# M26_M_V1_0.net
KiCad netlist of a schematic drawn in Altium Designer
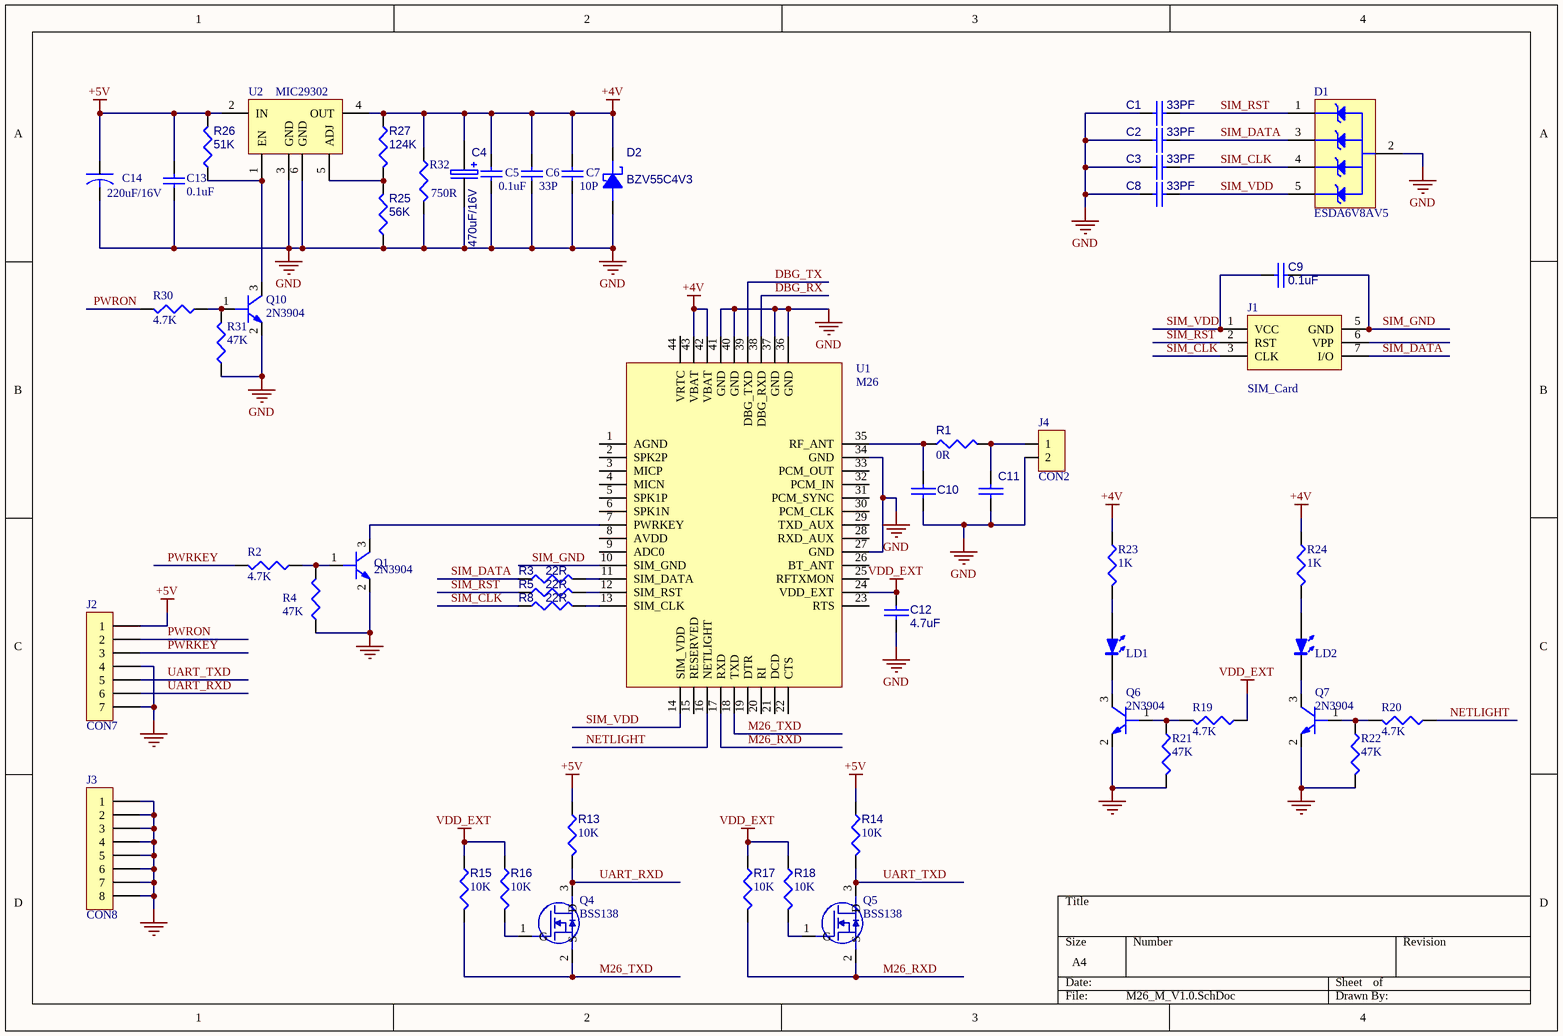
[diagram p0: M26_M_V1.0.SchDoc]

(export (version "E")
  (design (tool "Eeschema 10.0.6"))
  (components
    (comp (ref "C1")
      (value "33PF")
      (footprint "0603_C")
      (description "CAP")
      (libsource (lib "*") (part "CAP"))
    )
    (comp (ref "C2")
      (value "33PF")
      (footprint "0603_C")
      (description "CAP")
      (libsource (lib "*") (part "CAP"))
    )
    (comp (ref "C3")
      (value "33PF")
      (footprint "0603_C")
      (description "CAP")
      (libsource (lib "*") (part "CAP"))
    )
    (comp (ref "C4")
      (value "470uF/16V")
      (footprint "C_TAN_D")
      (description "E-CAP")
      (libsource (lib "*") (part "ECAP"))
    )
    (comp (ref "C5")
      (value "0.1uF")
      (footprint "0603_C")
      (description "Capacitor")
      (fields (field (name "PUBLISHER") "Altium Limited"))
      (libsource (lib "EP_MCB_V3.00") (part "Cap Semi"))
    )
    (comp (ref "C6")
      (value "33P")
      (footprint "0603_C")
      (description "Capacitor")
      (fields (field (name "PUBLISHER") "Altium Limited"))
      (libsource (lib "EP_MCB_V3.00") (part "Cap Semi"))
    )
    (comp (ref "C7")
      (value "10P")
      (footprint "0603_C")
      (description "Capacitor")
      (fields (field (name "PUBLISHER") "Altium Limited"))
      (libsource (lib "EP_MCB_V3.00") (part "Cap Semi"))
    )
    (comp (ref "C8")
      (value "33PF")
      (footprint "0603_C")
      (description "CAP")
      (libsource (lib "*") (part "CAP"))
    )
    (comp (ref "C9")
      (value "0.1uF")
      (footprint "0603_C")
      (description "CAP")
      (libsource (lib "*") (part "CAP"))
    )
    (comp (ref "C10")
      (value "NC")
      (footprint "0603_C")
      (description "CAP")
      (libsource (lib "") (part "CAP_1"))
    )
    (comp (ref "C11")
      (value "NC")
      (footprint "0603_C")
      (description "CAP")
      (libsource (lib "") (part "CAP_1"))
    )
    (comp (ref "C12")
      (value "4.7uF")
      (footprint "0603_C")
      (description "CAP")
      (libsource (lib "") (part "CAP_1"))
    )
    (comp (ref "C13")
      (value "0.1uF")
      (footprint "0603_C")
      (description "Capacitor")
      (fields (field (name "PUBLISHER") "Altium Limited"))
      (libsource (lib "EP_MCB_V3.00") (part "Cap Semi"))
    )
    (comp (ref "C14")
      (value "220uF/16V")
      (footprint "C_TAN_D")
      (libsource (lib "EM_SENSOR_V3.01") (part "C"))
    )
    (comp (ref "D1")
      (value "ESDA6V8AV5")
      (footprint "SOT-553")
      (libsource (lib "MySchlib") (part "ESDA6V8AV5"))
    )
    (comp (ref "D2")
      (value "BZV55C4V3")
      (footprint "SOD-80")
      (libsource (lib "EP_MCB_V4.1") (part "DIODE SCHOTTKY"))
    )
    (comp (ref "J1")
      (value "SIM_Card")
      (footprint "MicroSIM-6")
      (libsource (lib "MySchlib") (part "SIM_Card"))
    )
    (comp (ref "J2") (value "CON7") (footprint "SIP7") (libsource (lib "MySchlib") (part "CON7")))
    (comp (ref "J3") (value "CON8") (footprint "SIP-8") (libsource (lib "MySchlib") (part "CON8")))
    (comp (ref "J4") (value "CON2") (footprint "RF-Z") (libsource (lib "MySchlib") (part "CON2")))
    (comp (ref "LD1")
      (value "WHITE")
      (footprint "LED_0603")
      (description "LED")
      (libsource (lib "*") (part "LED"))
    )
    (comp (ref "LD2")
      (value "WHITE")
      (footprint "LED_0603")
      (description "LED")
      (libsource (lib "*") (part "LED"))
    )
    (comp (ref "Q1") (value "2N3904") (footprint "SOT23") (libsource (lib "MySchlib") (part "NPN")))
    (comp (ref "Q4")
      (value "BSS138")
      (footprint "SOT23")
      (description "N-Channel Enhancement MOSFET")
      (libsource (lib "EP_MCB_V6.0") (part "N-Channel Enhancement MOSFET"))
    )
    (comp (ref "Q5")
      (value "BSS138")
      (footprint "SOT23")
      (description "N-Channel Enhancement MOSFET")
      (libsource (lib "EP_MCB_V6.0") (part "N-Channel Enhancement MOSFET"))
    )
    (comp (ref "Q6") (value "2N3904") (footprint "SOT23") (libsource (lib "MySchlib") (part "NPN")))
    (comp (ref "Q7") (value "2N3904") (footprint "SOT23") (libsource (lib "MySchlib") (part "NPN")))
    (comp (ref "Q10") (value "2N3904") (footprint "SOT23") (libsource (lib "MySchlib") (part "NPN")))
    (comp (ref "R1")
      (value "0R")
      (footprint "0603_R")
      (description "Resistor")
      (fields (field (name "PUBLISHER") "Altium Limited"))
      (libsource (lib "EP_MCB_V6.0") (part "Res3_3"))
    )
    (comp (ref "R2") (value "4.7K") (footprint "0603_R") (libsource (lib "") (part "RES1_1")))
    (comp (ref "R3")
      (value "22R")
      (footprint "0603_R")
      (description "RESISTOR")
      (libsource (lib "*") (part "R0.25W"))
    )
    (comp (ref "R4") (value "47K") (footprint "0603_R") (libsource (lib "") (part "RES1_1")))
    (comp (ref "R5")
      (value "22R")
      (footprint "0603_R")
      (description "RESISTOR")
      (libsource (lib "*") (part "R0.25W"))
    )
    (comp (ref "R8")
      (value "22R")
      (footprint "0603_R")
      (description "RESISTOR")
      (libsource (lib "*") (part "R0.25W"))
    )
    (comp (ref "R13")
      (value "10K")
      (footprint "0603_R")
      (description "Resistor")
      (fields (field (name "PUBLISHER") "Altium Limited"))
      (libsource (lib "EP_MCB_V6.0") (part "Res3_3"))
    )
    (comp (ref "R14")
      (value "10K")
      (footprint "0603_R")
      (description "Resistor")
      (fields (field (name "PUBLISHER") "Altium Limited"))
      (libsource (lib "EP_MCB_V6.0") (part "Res3_3"))
    )
    (comp (ref "R15")
      (value "10K")
      (footprint "0603_R")
      (description "Resistor")
      (fields (field (name "PUBLISHER") "Altium Limited"))
      (libsource (lib "EP_MCB_V6.0") (part "Res3_3"))
    )
    (comp (ref "R16")
      (value "10K")
      (footprint "0603_R")
      (description "Resistor")
      (fields (field (name "PUBLISHER") "Altium Limited"))
      (libsource (lib "EP_MCB_V6.0") (part "Res3_3"))
    )
    (comp (ref "R17")
      (value "10K")
      (footprint "0603_R")
      (description "Resistor")
      (fields (field (name "PUBLISHER") "Altium Limited"))
      (libsource (lib "EP_MCB_V6.0") (part "Res3_3"))
    )
    (comp (ref "R18")
      (value "10K")
      (footprint "0603_R")
      (description "Resistor")
      (fields (field (name "PUBLISHER") "Altium Limited"))
      (libsource (lib "EP_MCB_V6.0") (part "Res3_3"))
    )
    (comp (ref "R19") (value "4.7K") (footprint "0603_R") (libsource (lib "") (part "RES1_1")))
    (comp (ref "R20") (value "4.7K") (footprint "0603_R") (libsource (lib "") (part "RES1_1")))
    (comp (ref "R21") (value "47K") (footprint "0603_R") (libsource (lib "") (part "RES1_1")))
    (comp (ref "R22") (value "47K") (footprint "0603_R") (libsource (lib "") (part "RES1_1")))
    (comp (ref "R23") (value "1K") (footprint "0603_R") (libsource (lib "") (part "RES1_1")))
    (comp (ref "R24") (value "1K") (footprint "0603_R") (libsource (lib "") (part "RES1_1")))
    (comp (ref "R25")
      (value "56K")
      (footprint "0603_R")
      (description "RESISTOR")
      (libsource (lib "*") (part "R0.25W"))
    )
    (comp (ref "R26")
      (value "51K")
      (footprint "0603_R")
      (description "RESISTOR")
      (libsource (lib "*") (part "R0.25W"))
    )
    (comp (ref "R27")
      (value "124K")
      (footprint "0603_R")
      (description "RESISTOR")
      (libsource (lib "*") (part "R0.25W"))
    )
    (comp (ref "R30") (value "4.7K") (footprint "0603_R") (libsource (lib "") (part "RES1_1")))
    (comp (ref "R31") (value "47K") (footprint "0603_R") (libsource (lib "") (part "RES1_1")))
    (comp (ref "R32") (value "750R") (footprint "0603_R") (libsource (lib "MySchlib") (part "RES1")))
    (comp (ref "U1") (value "M26") (footprint "M26") (libsource (lib "MySchlib") (part "M26")))
    (comp (ref "U2") (value "MIC29302") (footprint "TO-263-5") (libsource (lib "MySchlib") (part "MIC29302")))
  )
  (nets
    (net (code "1") (name "+4V") (class "Default")
      (node (ref "C4") (pin "1") (pinfunction "+_1") (pintype "passive"))
      (node (ref "C5") (pin "2") (pinfunction "2_2") (pintype "passive"))
      (node (ref "C6") (pin "2") (pinfunction "2_2") (pintype "passive"))
      (node (ref "C7") (pin "2") (pinfunction "2_2") (pintype "passive"))
      (node (ref "D2") (pin "2") (pinfunction "CATHODE_2") (pintype "passive"))
      (node (ref "R23") (pin "1") (pinfunction "1_1") (pintype "passive"))
      (node (ref "R24") (pin "1") (pinfunction "1_1") (pintype "passive"))
      (node (ref "R27") (pin "2") (pinfunction "2_2") (pintype "passive"))
      (node (ref "R32") (pin "2") (pinfunction "2_2") (pintype "passive"))
      (node (ref "U1") (pin "42") (pinfunction "VBAT_42") (pintype "passive"))
      (node (ref "U1") (pin "43") (pinfunction "VBAT_43") (pintype "passive"))
      (node (ref "U2") (pin "4") (pinfunction "OUT_4") (pintype "passive"))
    )
    (net (code "2") (name "+5V") (class "Default")
      (node (ref "C13") (pin "2") (pinfunction "2_2") (pintype "passive"))
      (node (ref "C14") (pin "1") (pinfunction "1_1") (pintype "passive"))
      (node (ref "J2") (pin "1") (pinfunction "1_1") (pintype "passive"))
      (node (ref "R13") (pin "1") (pinfunction "1_1") (pintype "passive"))
      (node (ref "R14") (pin "1") (pinfunction "1_1") (pintype "passive"))
      (node (ref "R26") (pin "1") (pinfunction "1_1") (pintype "passive"))
      (node (ref "U2") (pin "2") (pinfunction "IN_2") (pintype "passive"))
    )
    (net (code "3") (name "/DBG_RX") (class "Default")
      (node (ref "U1") (pin "38") (pinfunction "DBG_RXD_38") (pintype "passive"))
    )
    (net (code "4") (name "/DBG_TX") (class "Default")
      (node (ref "U1") (pin "39") (pinfunction "DBG_TXD_39") (pintype "passive"))
    )
    (net (code "5") (name "/M26_RXD") (class "Default")
      (node (ref "Q5") (pin "2") (pinfunction "S_2") (pintype "passive"))
      (node (ref "R17") (pin "2") (pinfunction "2_2") (pintype "passive"))
      (node (ref "U1") (pin "17") (pinfunction "RXD_17") (pintype "passive"))
    )
    (net (code "6") (name "/M26_TXD") (class "Default")
      (node (ref "Q4") (pin "2") (pinfunction "S_2") (pintype "passive"))
      (node (ref "R15") (pin "2") (pinfunction "2_2") (pintype "passive"))
      (node (ref "U1") (pin "18") (pinfunction "TXD_18") (pintype "passive"))
    )
    (net (code "7") (name "/NETLIGHT") (class "Default")
      (node (ref "R20") (pin "1") (pinfunction "1_1") (pintype "passive"))
      (node (ref "U1") (pin "16") (pinfunction "NETLIGHT_16") (pintype "passive"))
    )
    (net (code "8") (name "/PWRKEY") (class "Default")
      (node (ref "J2") (pin "3") (pinfunction "3_3") (pintype "passive"))
      (node (ref "R2") (pin "1") (pinfunction "1_1") (pintype "passive"))
    )
    (net (code "9") (name "/PWRON") (class "Default")
      (node (ref "J2") (pin "2") (pinfunction "2_2") (pintype "passive"))
      (node (ref "R30") (pin "1") (pinfunction "1_1") (pintype "passive"))
    )
    (net (code "10") (name "/SIM_CLK") (class "Default")
      (node (ref "C3") (pin "2") (pinfunction "2_2") (pintype "passive"))
      (node (ref "D1") (pin "4") (pinfunction "4_4") (pintype "passive"))
      (node (ref "J1") (pin "3") (pinfunction "CLK_3") (pintype "passive"))
      (node (ref "R8") (pin "1") (pinfunction "1_1") (pintype "passive"))
    )
    (net (code "11") (name "/SIM_DATA") (class "Default")
      (node (ref "C2") (pin "2") (pinfunction "2_2") (pintype "passive"))
      (node (ref "D1") (pin "3") (pinfunction "3_3") (pintype "passive"))
      (node (ref "J1") (pin "7") (pinfunction "I/O_7") (pintype "passive"))
      (node (ref "R3") (pin "1") (pinfunction "1_1") (pintype "passive"))
    )
    (net (code "12") (name "/SIM_GND") (class "Default")
      (node (ref "C9") (pin "2") (pinfunction "2_2") (pintype "passive"))
      (node (ref "J1") (pin "5") (pinfunction "GND_5") (pintype "passive"))
      (node (ref "U1") (pin "10") (pinfunction "SIM_GND_10") (pintype "passive"))
    )
    (net (code "13") (name "/SIM_RST") (class "Default")
      (node (ref "C1") (pin "2") (pinfunction "2_2") (pintype "passive"))
      (node (ref "D1") (pin "1") (pinfunction "1_1") (pintype "passive"))
      (node (ref "J1") (pin "2") (pinfunction "RST_2") (pintype "passive"))
      (node (ref "R5") (pin "1") (pinfunction "1_1") (pintype "passive"))
    )
    (net (code "14") (name "/SIM_VDD") (class "Default")
      (node (ref "C8") (pin "2") (pinfunction "2_2") (pintype "passive"))
      (node (ref "C9") (pin "1") (pinfunction "1_1") (pintype "passive"))
      (node (ref "D1") (pin "5") (pinfunction "5_5") (pintype "passive"))
      (node (ref "J1") (pin "1") (pinfunction "VCC_1") (pintype "passive"))
      (node (ref "U1") (pin "14") (pinfunction "SIM_VDD_14") (pintype "passive"))
    )
    (net (code "15") (name "/UART_RXD") (class "Default")
      (node (ref "J2") (pin "6") (pinfunction "6_6") (pintype "passive"))
      (node (ref "Q4") (pin "3") (pinfunction "D_3") (pintype "passive"))
      (node (ref "R13") (pin "2") (pinfunction "2_2") (pintype "passive"))
    )
    (net (code "16") (name "/UART_TXD") (class "Default")
      (node (ref "J2") (pin "5") (pinfunction "5_5") (pintype "passive"))
      (node (ref "Q5") (pin "3") (pinfunction "D_3") (pintype "passive"))
      (node (ref "R14") (pin "2") (pinfunction "2_2") (pintype "passive"))
    )
    (net (code "17") (name "GND") (class "Default")
      (node (ref "C1") (pin "1") (pinfunction "1_1") (pintype "passive"))
      (node (ref "C10") (pin "2") (pinfunction "2_2") (pintype "passive"))
      (node (ref "C11") (pin "2") (pinfunction "2_2") (pintype "passive"))
      (node (ref "C12") (pin "2") (pinfunction "2_2") (pintype "passive"))
      (node (ref "C13") (pin "1") (pinfunction "1_1") (pintype "passive"))
      (node (ref "C14") (pin "2") (pinfunction "2_2") (pintype "passive"))
      (node (ref "C2") (pin "1") (pinfunction "1_1") (pintype "passive"))
      (node (ref "C3") (pin "1") (pinfunction "1_1") (pintype "passive"))
      (node (ref "C4") (pin "2") (pinfunction "-_2") (pintype "passive"))
      (node (ref "C5") (pin "1") (pinfunction "1_1") (pintype "passive"))
      (node (ref "C6") (pin "1") (pinfunction "1_1") (pintype "passive"))
      (node (ref "C7") (pin "1") (pinfunction "1_1") (pintype "passive"))
      (node (ref "C8") (pin "1") (pinfunction "1_1") (pintype "passive"))
      (node (ref "D1") (pin "2") (pinfunction "2_2") (pintype "passive"))
      (node (ref "D2") (pin "1") (pinfunction "ANODE_1") (pintype "passive"))
      (node (ref "J2") (pin "4") (pinfunction "4_4") (pintype "passive"))
      (node (ref "J2") (pin "7") (pinfunction "7_7") (pintype "passive"))
      (node (ref "J3") (pin "1") (pinfunction "1_1") (pintype "passive"))
      (node (ref "J3") (pin "2") (pinfunction "2_2") (pintype "passive"))
      (node (ref "J3") (pin "3") (pinfunction "3_3") (pintype "passive"))
      (node (ref "J3") (pin "4") (pinfunction "4_4") (pintype "passive"))
      (node (ref "J3") (pin "5") (pinfunction "5_5") (pintype "passive"))
      (node (ref "J3") (pin "6") (pinfunction "6_6") (pintype "passive"))
      (node (ref "J3") (pin "7") (pinfunction "7_7") (pintype "passive"))
      (node (ref "J3") (pin "8") (pinfunction "8_8") (pintype "passive"))
      (node (ref "J4") (pin "2") (pinfunction "2_2") (pintype "passive"))
      (node (ref "Q1") (pin "2") (pinfunction "EMITTER_2") (pintype "passive"))
      (node (ref "Q10") (pin "2") (pinfunction "EMITTER_2") (pintype "passive"))
      (node (ref "Q6") (pin "2") (pinfunction "EMITTER_2") (pintype "passive"))
      (node (ref "Q7") (pin "2") (pinfunction "EMITTER_2") (pintype "passive"))
      (node (ref "R21") (pin "2") (pinfunction "2_2") (pintype "passive"))
      (node (ref "R22") (pin "2") (pinfunction "2_2") (pintype "passive"))
      (node (ref "R25") (pin "2") (pinfunction "2_2") (pintype "passive"))
      (node (ref "R31") (pin "2") (pinfunction "2_2") (pintype "passive"))
      (node (ref "R32") (pin "1") (pinfunction "1_1") (pintype "passive"))
      (node (ref "R4") (pin "2") (pinfunction "2_2") (pintype "passive"))
      (node (ref "U1") (pin "27") (pinfunction "GND_27") (pintype "passive"))
      (node (ref "U1") (pin "34") (pinfunction "GND_34") (pintype "passive"))
      (node (ref "U1") (pin "36") (pinfunction "GND_36") (pintype "passive"))
      (node (ref "U1") (pin "37") (pinfunction "GND_37") (pintype "passive"))
      (node (ref "U1") (pin "40") (pinfunction "GND_40") (pintype "passive"))
      (node (ref "U1") (pin "41") (pinfunction "GND_41") (pintype "passive"))
      (node (ref "U2") (pin "3") (pinfunction "GND_3") (pintype "passive"))
      (node (ref "U2") (pin "6") (pinfunction "GND_6") (pintype "passive"))
    )
    (net (code "18") (name "Net-(C11-Pad1)") (class "Default")
      (node (ref "C11") (pin "1") (pinfunction "1_1") (pintype "passive"))
      (node (ref "J4") (pin "1") (pinfunction "1_1") (pintype "passive"))
      (node (ref "R1") (pin "2") (pinfunction "2_2") (pintype "passive"))
    )
    (net (code "19") (name "Net-(LD1-PadA)") (class "Default")
      (node (ref "LD1") (pin "A") (pinfunction "A_A") (pintype "passive"))
      (node (ref "R23") (pin "2") (pinfunction "2_2") (pintype "passive"))
    )
    (net (code "20") (name "Net-(LD2-PadA)") (class "Default")
      (node (ref "LD2") (pin "A") (pinfunction "A_A") (pintype "passive"))
      (node (ref "R24") (pin "2") (pinfunction "2_2") (pintype "passive"))
    )
    (net (code "21") (name "Net-(Q1-BASE)") (class "Default")
      (node (ref "Q1") (pin "1") (pinfunction "BASE_1") (pintype "passive"))
      (node (ref "R2") (pin "2") (pinfunction "2_2") (pintype "passive"))
      (node (ref "R4") (pin "1") (pinfunction "1_1") (pintype "passive"))
    )
    (net (code "22") (name "Net-(Q1-COLLECTOR)") (class "Default")
      (node (ref "Q1") (pin "3") (pinfunction "COLLECTOR_3") (pintype "passive"))
      (node (ref "U1") (pin "7") (pinfunction "PWRKEY_7") (pintype "passive"))
    )
    (net (code "23") (name "Net-(Q4-G)") (class "Default")
      (node (ref "Q4") (pin "1") (pinfunction "G_1") (pintype "passive"))
      (node (ref "R16") (pin "2") (pinfunction "2_2") (pintype "passive"))
    )
    (net (code "24") (name "Net-(Q5-G)") (class "Default")
      (node (ref "Q5") (pin "1") (pinfunction "G_1") (pintype "passive"))
      (node (ref "R18") (pin "2") (pinfunction "2_2") (pintype "passive"))
    )
    (net (code "25") (name "Net-(Q6-BASE)") (class "Default")
      (node (ref "Q6") (pin "1") (pinfunction "BASE_1") (pintype "passive"))
      (node (ref "R19") (pin "2") (pinfunction "2_2") (pintype "passive"))
      (node (ref "R21") (pin "1") (pinfunction "1_1") (pintype "passive"))
    )
    (net (code "26") (name "Net-(Q6-COLLECTOR)") (class "Default")
      (node (ref "LD1") (pin "K") (pinfunction "K_K") (pintype "passive"))
      (node (ref "Q6") (pin "3") (pinfunction "COLLECTOR_3") (pintype "passive"))
    )
    (net (code "27") (name "Net-(Q7-BASE)") (class "Default")
      (node (ref "Q7") (pin "1") (pinfunction "BASE_1") (pintype "passive"))
      (node (ref "R20") (pin "2") (pinfunction "2_2") (pintype "passive"))
      (node (ref "R22") (pin "1") (pinfunction "1_1") (pintype "passive"))
    )
    (net (code "28") (name "Net-(Q7-COLLECTOR)") (class "Default")
      (node (ref "LD2") (pin "K") (pinfunction "K_K") (pintype "passive"))
      (node (ref "Q7") (pin "3") (pinfunction "COLLECTOR_3") (pintype "passive"))
    )
    (net (code "29") (name "Net-(Q10-BASE)") (class "Default")
      (node (ref "Q10") (pin "1") (pinfunction "BASE_1") (pintype "passive"))
      (node (ref "R30") (pin "2") (pinfunction "2_2") (pintype "passive"))
      (node (ref "R31") (pin "1") (pinfunction "1_1") (pintype "passive"))
    )
    (net (code "30") (name "Net-(Q10-COLLECTOR)") (class "Default")
      (node (ref "Q10") (pin "3") (pinfunction "COLLECTOR_3") (pintype "passive"))
      (node (ref "R26") (pin "2") (pinfunction "2_2") (pintype "passive"))
      (node (ref "U2") (pin "1") (pinfunction "EN_1") (pintype "passive"))
    )
    (net (code "31") (name "Net-(U1-RF_ANT)") (class "Default")
      (node (ref "C10") (pin "1") (pinfunction "1_1") (pintype "passive"))
      (node (ref "R1") (pin "1") (pinfunction "1_1") (pintype "passive"))
      (node (ref "U1") (pin "35") (pinfunction "RF_ANT_35") (pintype "passive"))
    )
    (net (code "32") (name "Net-(U1-SIM_CLK)") (class "Default")
      (node (ref "R8") (pin "2") (pinfunction "2_2") (pintype "passive"))
      (node (ref "U1") (pin "13") (pinfunction "SIM_CLK_13") (pintype "passive"))
    )
    (net (code "33") (name "Net-(U1-SIM_DATA)") (class "Default")
      (node (ref "R3") (pin "2") (pinfunction "2_2") (pintype "passive"))
      (node (ref "U1") (pin "11") (pinfunction "SIM_DATA_11") (pintype "passive"))
    )
    (net (code "34") (name "Net-(U1-SIM_RST)") (class "Default")
      (node (ref "R5") (pin "2") (pinfunction "2_2") (pintype "passive"))
      (node (ref "U1") (pin "12") (pinfunction "SIM_RST_12") (pintype "passive"))
    )
    (net (code "35") (name "Net-(U2-ADJ)") (class "Default")
      (node (ref "R25") (pin "1") (pinfunction "1_1") (pintype "passive"))
      (node (ref "R27") (pin "1") (pinfunction "1_1") (pintype "passive"))
      (node (ref "U2") (pin "5") (pinfunction "ADJ_5") (pintype "passive"))
    )
    (net (code "36") (name "VDD_EXT") (class "Default")
      (node (ref "C12") (pin "1") (pinfunction "1_1") (pintype "passive"))
      (node (ref "R15") (pin "1") (pinfunction "1_1") (pintype "passive"))
      (node (ref "R16") (pin "1") (pinfunction "1_1") (pintype "passive"))
      (node (ref "R17") (pin "1") (pinfunction "1_1") (pintype "passive"))
      (node (ref "R18") (pin "1") (pinfunction "1_1") (pintype "passive"))
      (node (ref "R19") (pin "1") (pinfunction "1_1") (pintype "passive"))
      (node (ref "U1") (pin "24") (pinfunction "VDD_EXT_24") (pintype "passive"))
    )
    (net (code "37") (name "unconnected-(J1-VPP-Pad6)") (class "Default")
      (node (ref "J1") (pin "6") (pinfunction "VPP_6") (pintype "passive"))
    )
    (net (code "38") (name "unconnected-(U1-ADC0-Pad9)") (class "Default")
      (node (ref "U1") (pin "9") (pinfunction "ADC0_9") (pintype "passive"))
    )
    (net (code "39") (name "unconnected-(U1-AGND-Pad1)") (class "Default")
      (node (ref "U1") (pin "1") (pinfunction "AGND_1") (pintype "passive"))
    )
    (net (code "40") (name "unconnected-(U1-AVDD-Pad8)") (class "Default")
      (node (ref "U1") (pin "8") (pinfunction "AVDD_8") (pintype "passive"))
    )
    (net (code "41") (name "unconnected-(U1-BT_ANT-Pad26)") (class "Default")
      (node (ref "U1") (pin "26") (pinfunction "BT_ANT_26") (pintype "passive"))
    )
    (net (code "42") (name "unconnected-(U1-CTS-Pad22)") (class "Default")
      (node (ref "U1") (pin "22") (pinfunction "CTS_22") (pintype "passive"))
    )
    (net (code "43") (name "unconnected-(U1-DCD-Pad21)") (class "Default")
      (node (ref "U1") (pin "21") (pinfunction "DCD_21") (pintype "passive"))
    )
    (net (code "44") (name "unconnected-(U1-DTR-Pad19)") (class "Default")
      (node (ref "U1") (pin "19") (pinfunction "DTR_19") (pintype "passive"))
    )
    (net (code "45") (name "unconnected-(U1-MICN-Pad4)") (class "Default")
      (node (ref "U1") (pin "4") (pinfunction "MICN_4") (pintype "passive"))
    )
    (net (code "46") (name "unconnected-(U1-MICP-Pad3)") (class "Default")
      (node (ref "U1") (pin "3") (pinfunction "MICP_3") (pintype "passive"))
    )
    (net (code "47") (name "unconnected-(U1-PCM_CLK-Pad30)") (class "Default")
      (node (ref "U1") (pin "30") (pinfunction "PCM_CLK_30") (pintype "passive"))
    )
    (net (code "48") (name "unconnected-(U1-PCM_IN-Pad32)") (class "Default")
      (node (ref "U1") (pin "32") (pinfunction "PCM_IN_32") (pintype "passive"))
    )
    (net (code "49") (name "unconnected-(U1-PCM_OUT-Pad33)") (class "Default")
      (node (ref "U1") (pin "33") (pinfunction "PCM_OUT_33") (pintype "passive"))
    )
    (net (code "50") (name "unconnected-(U1-PCM_SYNC-Pad31)") (class "Default")
      (node (ref "U1") (pin "31") (pinfunction "PCM_SYNC_31") (pintype "passive"))
    )
    (net (code "51") (name "unconnected-(U1-RESERVED-Pad15)") (class "Default")
      (node (ref "U1") (pin "15") (pinfunction "RESERVED_15") (pintype "passive"))
    )
    (net (code "52") (name "unconnected-(U1-RFTXMON-Pad25)") (class "Default")
      (node (ref "U1") (pin "25") (pinfunction "RFTXMON_25") (pintype "passive"))
    )
    (net (code "53") (name "unconnected-(U1-RI-Pad20)") (class "Default")
      (node (ref "U1") (pin "20") (pinfunction "RI_20") (pintype "passive"))
    )
    (net (code "54") (name "unconnected-(U1-RTS-Pad23)") (class "Default")
      (node (ref "U1") (pin "23") (pinfunction "RTS_23") (pintype "passive"))
    )
    (net (code "55") (name "unconnected-(U1-RXD_AUX-Pad28)") (class "Default")
      (node (ref "U1") (pin "28") (pinfunction "RXD_AUX_28") (pintype "passive"))
    )
    (net (code "56") (name "unconnected-(U1-SPK1N-Pad6)") (class "Default")
      (node (ref "U1") (pin "6") (pinfunction "SPK1N_6") (pintype "passive"))
    )
    (net (code "57") (name "unconnected-(U1-SPK1P-Pad5)") (class "Default")
      (node (ref "U1") (pin "5") (pinfunction "SPK1P_5") (pintype "passive"))
    )
    (net (code "58") (name "unconnected-(U1-SPK2P-Pad2)") (class "Default")
      (node (ref "U1") (pin "2") (pinfunction "SPK2P_2") (pintype "passive"))
    )
    (net (code "59") (name "unconnected-(U1-TXD_AUX-Pad29)") (class "Default")
      (node (ref "U1") (pin "29") (pinfunction "TXD_AUX_29") (pintype "passive"))
    )
    (net (code "60") (name "unconnected-(U1-VRTC-Pad44)") (class "Default")
      (node (ref "U1") (pin "44") (pinfunction "VRTC_44") (pintype "passive"))
    )
  )
)
